# brain_v01.net
KiCad netlist of a schematic drawn in EAGLE
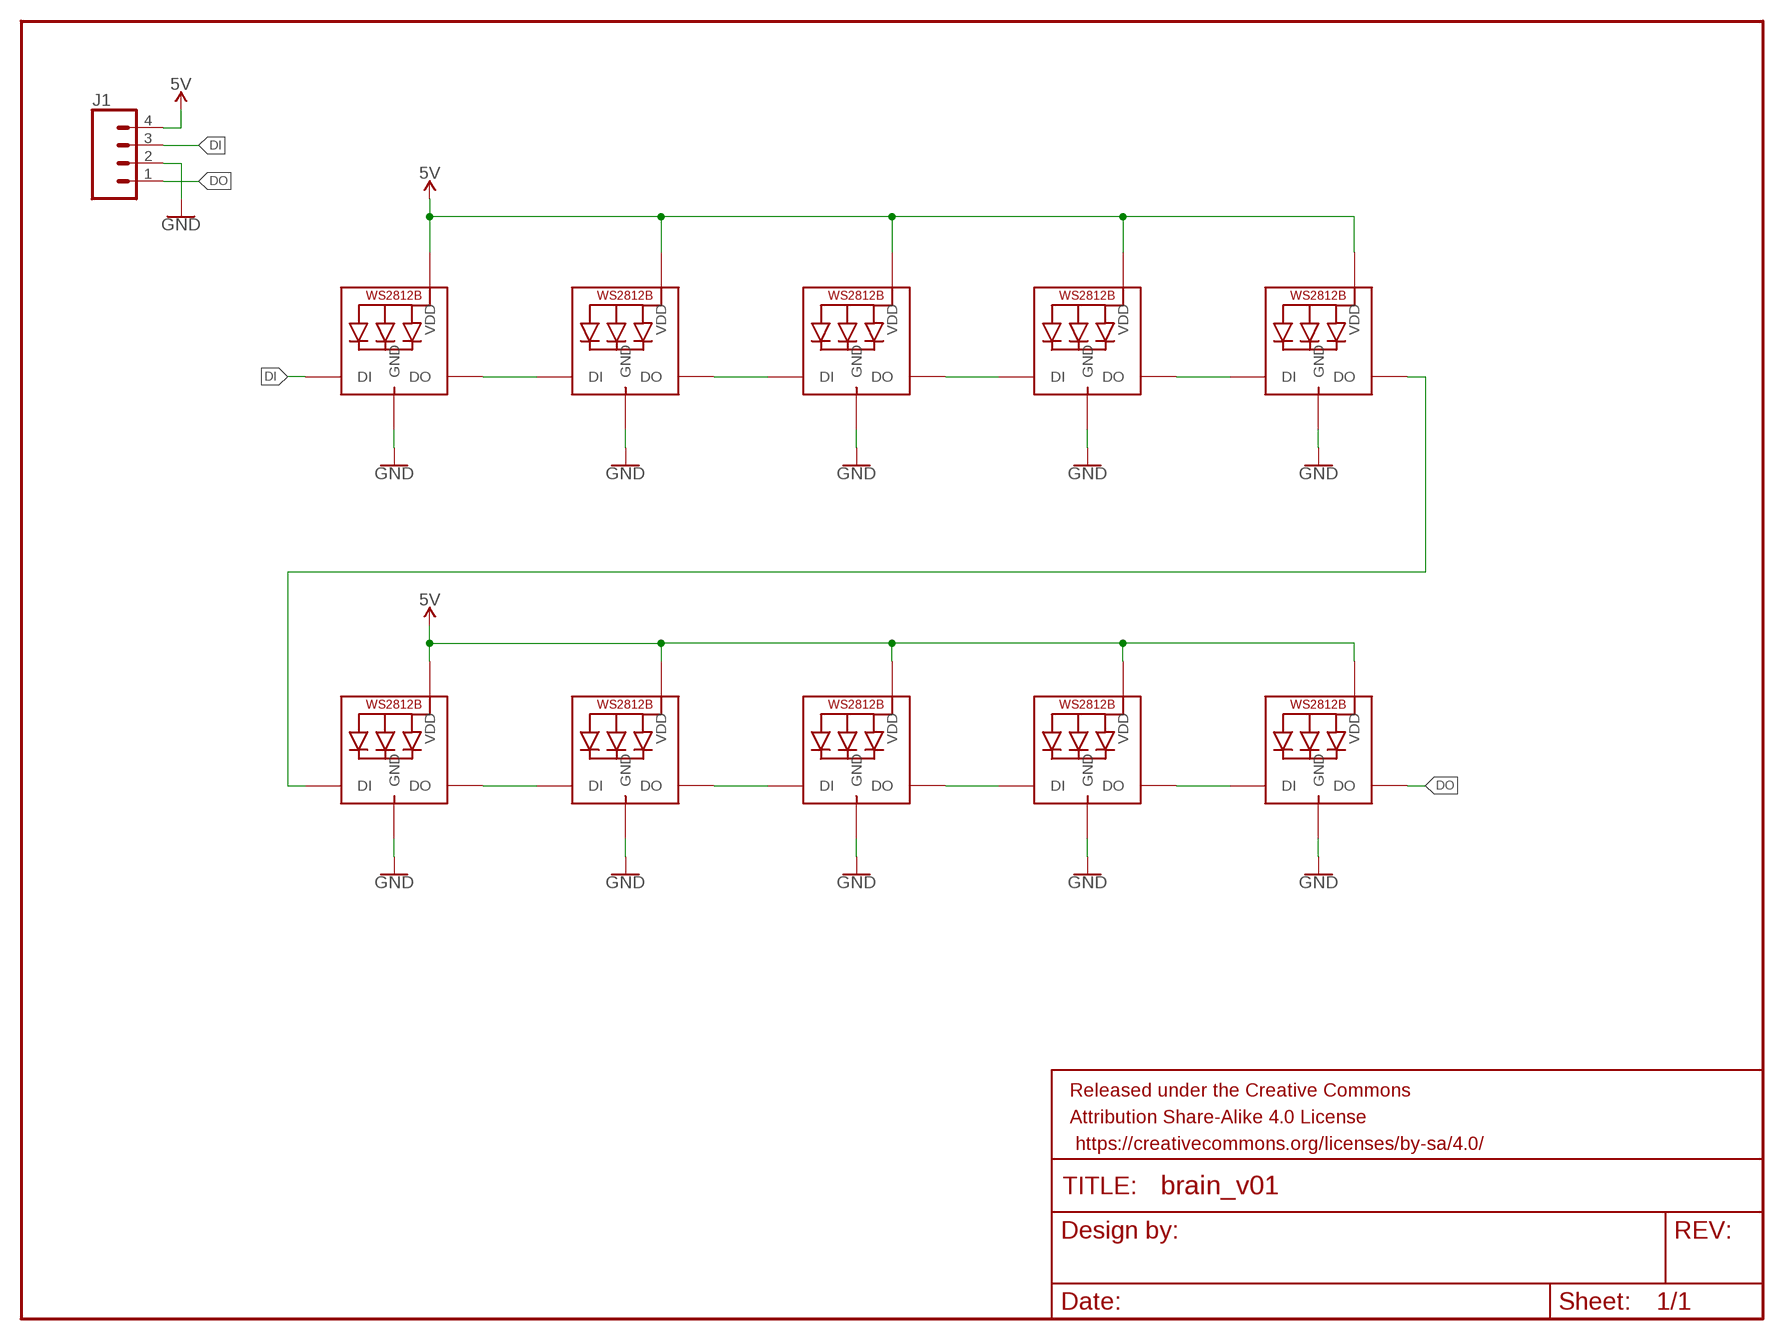
[diagram p0: schematic, sheet 1]

(export (version "E")
  (design (tool "Eeschema 10.0.6"))
  (components
    (comp (ref "FRAME1")
      (value "FRAME-LETTER")
      (footprint "eagle-import:CREATIVE_COMMONS")
      (libsource (lib "eagle-import") (part "FRAME-LETTER"))
    )
    (comp (ref "J1")
      (value "CONN_04PTH")
      (footprint "eagle-import:1X04")
      (libsource (lib "eagle-import") (part "CONN_04PTH"))
    )
    (comp (ref "LED1")
      (value "WS2812B3535")
      (footprint "eagle-import:LED3535")
      (libsource (lib "eagle-import") (part "WS2812B3535"))
    )
    (comp (ref "LED2")
      (value "WS2812B3535")
      (footprint "eagle-import:LED3535")
      (libsource (lib "eagle-import") (part "WS2812B3535"))
    )
    (comp (ref "LED3")
      (value "WS2812B3535")
      (footprint "eagle-import:LED3535")
      (libsource (lib "eagle-import") (part "WS2812B3535"))
    )
    (comp (ref "LED4")
      (value "WS2812B3535")
      (footprint "eagle-import:LED3535")
      (libsource (lib "eagle-import") (part "WS2812B3535"))
    )
    (comp (ref "LED5")
      (value "WS2812B3535")
      (footprint "eagle-import:LED3535")
      (libsource (lib "eagle-import") (part "WS2812B3535"))
    )
    (comp (ref "LED6")
      (value "WS2812B3535")
      (footprint "eagle-import:LED3535")
      (libsource (lib "eagle-import") (part "WS2812B3535"))
    )
    (comp (ref "LED7")
      (value "WS2812B3535")
      (footprint "eagle-import:LED3535")
      (libsource (lib "eagle-import") (part "WS2812B3535"))
    )
    (comp (ref "LED8")
      (value "WS2812B3535")
      (footprint "eagle-import:LED3535")
      (libsource (lib "eagle-import") (part "WS2812B3535"))
    )
    (comp (ref "LED9")
      (value "WS2812B3535")
      (footprint "eagle-import:LED3535")
      (libsource (lib "eagle-import") (part "WS2812B3535"))
    )
    (comp (ref "LED10")
      (value "WS2812B3535")
      (footprint "eagle-import:LED3535")
      (libsource (lib "eagle-import") (part "WS2812B3535"))
    )
  )
  (nets
    (net (code "1") (name "5V") (class "Default")
      (node (ref "J1") (pin "4") (pinfunction "4_4") (pintype "passive"))
      (node (ref "LED1") (pin "2") (pinfunction "VDD_2") (pintype "power_in"))
      (node (ref "LED10") (pin "2") (pinfunction "VDD_2") (pintype "power_in"))
      (node (ref "LED2") (pin "2") (pinfunction "VDD_2") (pintype "power_in"))
      (node (ref "LED3") (pin "2") (pinfunction "VDD_2") (pintype "power_in"))
      (node (ref "LED4") (pin "2") (pinfunction "VDD_2") (pintype "power_in"))
      (node (ref "LED5") (pin "2") (pinfunction "VDD_2") (pintype "power_in"))
      (node (ref "LED6") (pin "2") (pinfunction "VDD_2") (pintype "power_in"))
      (node (ref "LED7") (pin "2") (pinfunction "VDD_2") (pintype "power_in"))
      (node (ref "LED8") (pin "2") (pinfunction "VDD_2") (pintype "power_in"))
      (node (ref "LED9") (pin "2") (pinfunction "VDD_2") (pintype "power_in"))
    )
    (net (code "2") (name "DI") (class "Default")
      (node (ref "J1") (pin "3") (pinfunction "3_3") (pintype "passive"))
      (node (ref "LED1") (pin "1") (pinfunction "DI_1") (pintype "input"))
    )
    (net (code "3") (name "DO") (class "Default")
      (node (ref "J1") (pin "1") (pinfunction "1_1") (pintype "passive"))
      (node (ref "LED10") (pin "3") (pinfunction "DO_3") (pintype "output"))
    )
    (net (code "4") (name "GND") (class "Default")
      (node (ref "J1") (pin "2") (pinfunction "2_2") (pintype "passive"))
      (node (ref "LED1") (pin "4") (pinfunction "GND_4") (pintype "power_in"))
      (node (ref "LED10") (pin "4") (pinfunction "GND_4") (pintype "power_in"))
      (node (ref "LED2") (pin "4") (pinfunction "GND_4") (pintype "power_in"))
      (node (ref "LED3") (pin "4") (pinfunction "GND_4") (pintype "power_in"))
      (node (ref "LED4") (pin "4") (pinfunction "GND_4") (pintype "power_in"))
      (node (ref "LED5") (pin "4") (pinfunction "GND_4") (pintype "power_in"))
      (node (ref "LED6") (pin "4") (pinfunction "GND_4") (pintype "power_in"))
      (node (ref "LED7") (pin "4") (pinfunction "GND_4") (pintype "power_in"))
      (node (ref "LED8") (pin "4") (pinfunction "GND_4") (pintype "power_in"))
      (node (ref "LED9") (pin "4") (pinfunction "GND_4") (pintype "power_in"))
    )
    (net (code "5") (name "Net-(LED1-DO)") (class "Default")
      (node (ref "LED1") (pin "3") (pinfunction "DO_3") (pintype "output"))
      (node (ref "LED2") (pin "1") (pinfunction "DI_1") (pintype "input"))
    )
    (net (code "6") (name "Net-(LED2-DO)") (class "Default")
      (node (ref "LED2") (pin "3") (pinfunction "DO_3") (pintype "output"))
      (node (ref "LED3") (pin "1") (pinfunction "DI_1") (pintype "input"))
    )
    (net (code "7") (name "Net-(LED3-DO)") (class "Default")
      (node (ref "LED3") (pin "3") (pinfunction "DO_3") (pintype "output"))
      (node (ref "LED4") (pin "1") (pinfunction "DI_1") (pintype "input"))
    )
    (net (code "8") (name "Net-(LED4-DO)") (class "Default")
      (node (ref "LED4") (pin "3") (pinfunction "DO_3") (pintype "output"))
      (node (ref "LED5") (pin "1") (pinfunction "DI_1") (pintype "input"))
    )
    (net (code "9") (name "Net-(LED5-DO)") (class "Default")
      (node (ref "LED5") (pin "3") (pinfunction "DO_3") (pintype "output"))
      (node (ref "LED6") (pin "1") (pinfunction "DI_1") (pintype "input"))
    )
    (net (code "10") (name "Net-(LED6-DO)") (class "Default")
      (node (ref "LED6") (pin "3") (pinfunction "DO_3") (pintype "output"))
      (node (ref "LED7") (pin "1") (pinfunction "DI_1") (pintype "input"))
    )
    (net (code "11") (name "Net-(LED7-DO)") (class "Default")
      (node (ref "LED7") (pin "3") (pinfunction "DO_3") (pintype "output"))
      (node (ref "LED8") (pin "1") (pinfunction "DI_1") (pintype "input"))
    )
    (net (code "12") (name "Net-(LED8-DO)") (class "Default")
      (node (ref "LED8") (pin "3") (pinfunction "DO_3") (pintype "output"))
      (node (ref "LED9") (pin "1") (pinfunction "DI_1") (pintype "input"))
    )
    (net (code "13") (name "Net-(LED10-DI)") (class "Default")
      (node (ref "LED10") (pin "1") (pinfunction "DI_1") (pintype "input"))
      (node (ref "LED9") (pin "3") (pinfunction "DO_3") (pintype "output"))
    )
  )
)
